# switch_AT10.net
KiCad netlist of a schematic drawn in EAGLE
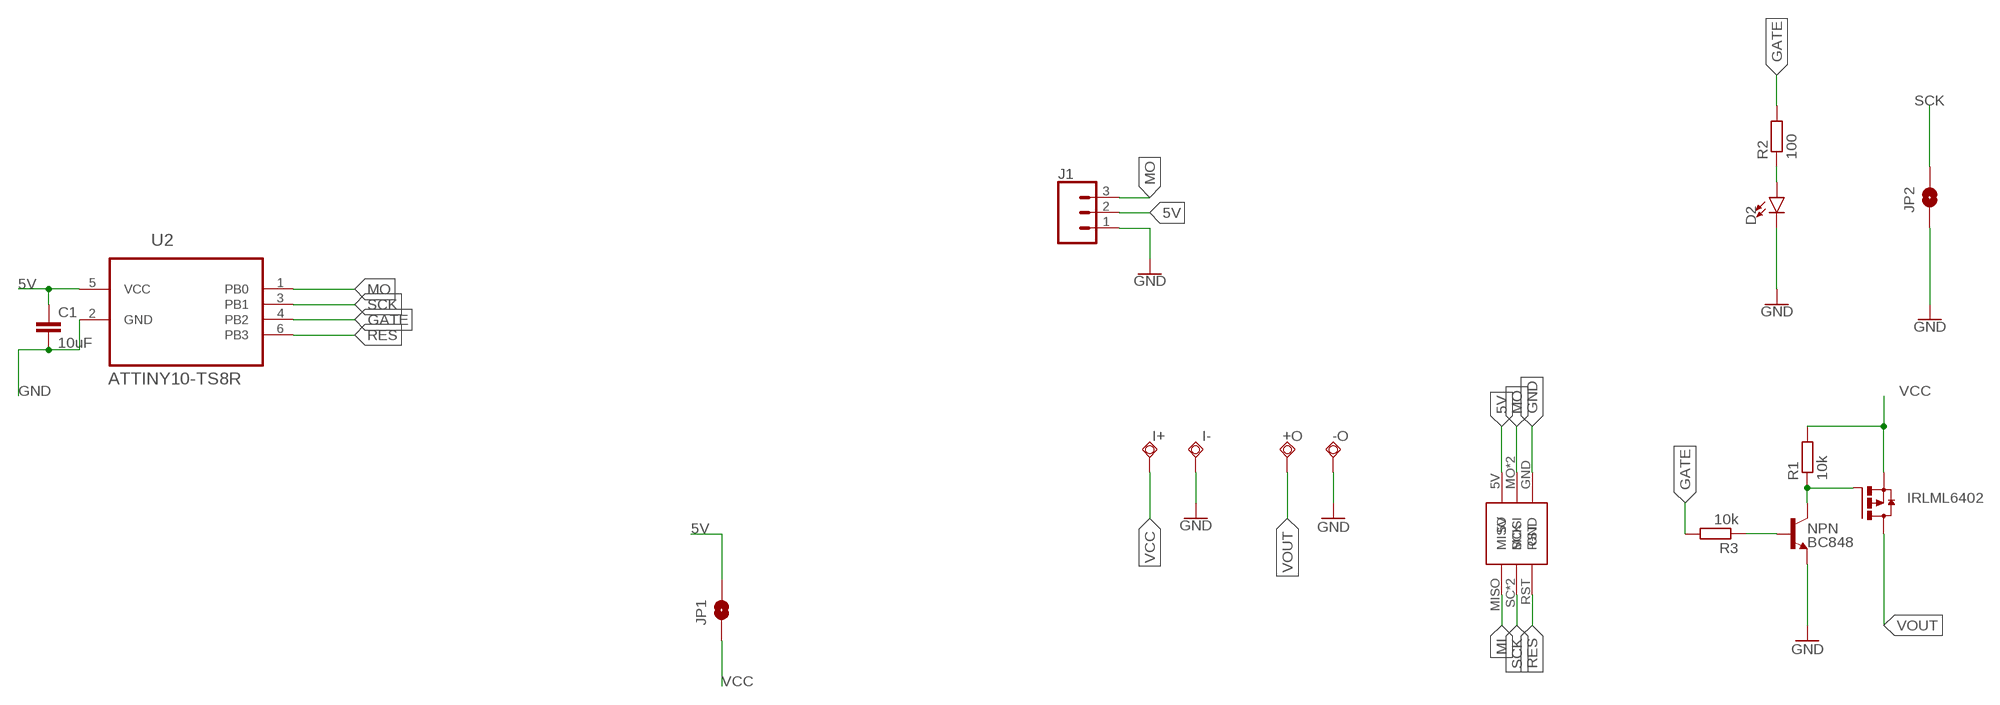
[diagram p0: schematic, sheet 1]

(export (version "E")
  (design (tool "Eeschema 10.0.6"))
  (components
    (comp (ref "+O")
      (value "TPSQTP20SQ")
      (footprint "eagle-import:TP20SQ")
      (libsource (lib "eagle-import") (part "TPSQTP20SQ"))
    )
    (comp (ref "-O")
      (value "TPSQTP20SQ")
      (footprint "eagle-import:TP20SQ")
      (libsource (lib "eagle-import") (part "TPSQTP20SQ"))
    )
    (comp (ref "C1")
      (value "10uF")
      (footprint "eagle-import:C0603K")
      (libsource (lib "eagle-import") (part "C-EUC0603K"))
    )
    (comp (ref "D2")
      (value "LED0603")
      (footprint "eagle-import:LED-0603")
      (libsource (lib "eagle-import") (part "LED0603"))
    )
    (comp (ref "I+")
      (value "TPSQTP20SQ")
      (footprint "eagle-import:TP20SQ")
      (libsource (lib "eagle-import") (part "TPSQTP20SQ"))
    )
    (comp (ref "I-")
      (value "TPSQTP20SQ")
      (footprint "eagle-import:TP20SQ")
      (libsource (lib "eagle-import") (part "TPSQTP20SQ"))
    )
    (comp (ref "IRLML6402")
      (value "FDN360P")
      (footprint "eagle-import:SUPER-SOT3")
      (libsource (lib "eagle-import") (part "FDN360P"))
    )
    (comp (ref "J1")
      (value "CONN_03")
      (footprint "eagle-import:1X03")
      (libsource (lib "eagle-import") (part "CONN_03"))
    )
    (comp (ref "JP1")
      (value "JUMPER-SMT_2_NO_NO-SILK")
      (footprint "eagle-import:SMT-JUMPER_2_NO_NO-SILK")
      (libsource (lib "eagle-import") (part "JUMPER-SMT_2_NO_NO-SILK"))
    )
    (comp (ref "JP2")
      (value "JUMPER-SMT_2_NO_NO-SILK")
      (footprint "eagle-import:SMT-JUMPER_2_NO_NO-SILK")
      (libsource (lib "eagle-import") (part "JUMPER-SMT_2_NO_NO-SILK"))
    )
    (comp (ref "NPN")
      (value "BC848")
      (footprint "eagle-import:SOT23-3")
      (libsource (lib "eagle-import") (part "TRANS_NPN-MMBT2222AL"))
    )
    (comp (ref "R1")
      (value "10k")
      (footprint "eagle-import:R0603")
      (libsource (lib "eagle-import") (part "R-EU_R0603"))
    )
    (comp (ref "R2")
      (value "100")
      (footprint "eagle-import:R0603")
      (libsource (lib "eagle-import") (part "R-EU_R0603"))
    )
    (comp (ref "R3")
      (value "10k")
      (footprint "eagle-import:R0603")
      (libsource (lib "eagle-import") (part "R-EU_R0603"))
    )
    (comp (ref "U$2")
      (value "ISCP_PORTPOGONEW")
      (footprint "eagle-import:ISCP_PADS_2ROW2HNEW")
      (libsource (lib "eagle-import") (part "ISCP_PORTPOGONEW"))
    )
    (comp (ref "U2")
      (value "ATTINY10-TS8R")
      (footprint "eagle-import:SOT95P280X145-6N")
      (fields (field (name "MF") "Microchip"))
      (libsource (lib "eagle-import") (part "ATTINY10-TS8R"))
    )
  )
  (nets
    (net (code "1") (name "5V") (class "Default")
      (node (ref "C1") (pin "1") (pinfunction "1_1") (pintype "passive"))
      (node (ref "J1") (pin "2") (pinfunction "2_2") (pintype "passive"))
      (node (ref "JP1") (pin "2") (pinfunction "2_2") (pintype "passive"))
      (node (ref "U$2") (pin "5V") (pinfunction "5V_5V") (pintype "bidirectional"))
      (node (ref "U2") (pin "5") (pinfunction "VCC_5") (pintype "power_in"))
    )
    (net (code "2") (name "GATE") (class "Default")
      (node (ref "R2") (pin "2") (pinfunction "2_2") (pintype "passive"))
      (node (ref "R3") (pin "2") (pinfunction "2_2") (pintype "passive"))
      (node (ref "U2") (pin "4") (pinfunction "PB2_4") (pintype "bidirectional"))
    )
    (net (code "3") (name "GND") (class "Default")
      (node (ref "-O") (pin "TP") (pinfunction "TP_TP") (pintype "input"))
      (node (ref "C1") (pin "2") (pinfunction "2_2") (pintype "passive"))
      (node (ref "D2") (pin "C") (pinfunction "C_C") (pintype "passive"))
      (node (ref "I-") (pin "TP") (pinfunction "TP_TP") (pintype "input"))
      (node (ref "J1") (pin "1") (pinfunction "1_1") (pintype "passive"))
      (node (ref "JP2") (pin "1") (pinfunction "1_1") (pintype "passive"))
      (node (ref "NPN") (pin "2") (pinfunction "E_2") (pintype "passive"))
      (node (ref "U$2") (pin "GND") (pinfunction "GND_GND") (pintype "bidirectional"))
      (node (ref "U2") (pin "2") (pinfunction "GND_2") (pintype "passive"))
    )
    (net (code "4") (name "MI") (class "Default")
      (node (ref "U$2") (pin "MISO") (pinfunction "MISO_MISO") (pintype "bidirectional"))
    )
    (net (code "5") (name "MO") (class "Default")
      (node (ref "J1") (pin "3") (pinfunction "3_3") (pintype "passive"))
      (node (ref "U$2") (pin "MO") (pinfunction "MOSI_MO") (pintype "bidirectional"))
      (node (ref "U$2") (pin "MOSI") (pinfunction "MOSI_MOSI") (pintype "bidirectional"))
      (node (ref "U2") (pin "1") (pinfunction "PB0_1") (pintype "bidirectional"))
    )
    (net (code "6") (name "Net-(D2-PadA)") (class "Default")
      (node (ref "D2") (pin "A") (pinfunction "A_A") (pintype "passive"))
      (node (ref "R2") (pin "1") (pinfunction "1_1") (pintype "passive"))
    )
    (net (code "7") (name "Net-(IRLML6402-G)") (class "Default")
      (node (ref "IRLML6402") (pin "1") (pinfunction "G_1") (pintype "passive"))
      (node (ref "NPN") (pin "3") (pinfunction "C_3") (pintype "passive"))
      (node (ref "R1") (pin "1") (pinfunction "1_1") (pintype "passive"))
    )
    (net (code "8") (name "Net-(NPN-B)") (class "Default")
      (node (ref "NPN") (pin "1") (pinfunction "B_1") (pintype "passive"))
      (node (ref "R3") (pin "1") (pinfunction "1_1") (pintype "passive"))
    )
    (net (code "9") (name "RES") (class "Default")
      (node (ref "U$2") (pin "RST") (pinfunction "RST_RST") (pintype "bidirectional"))
      (node (ref "U2") (pin "6") (pinfunction "PB3_6") (pintype "bidirectional"))
    )
    (net (code "10") (name "SCK") (class "Default")
      (node (ref "JP2") (pin "2") (pinfunction "2_2") (pintype "passive"))
      (node (ref "U$2") (pin "SC") (pinfunction "SCK_SC") (pintype "bidirectional"))
      (node (ref "U$2") (pin "SCK") (pinfunction "SCK_SCK") (pintype "bidirectional"))
      (node (ref "U2") (pin "3") (pinfunction "PB1_3") (pintype "bidirectional"))
    )
    (net (code "11") (name "VCC") (class "Default")
      (node (ref "I+") (pin "TP") (pinfunction "TP_TP") (pintype "input"))
      (node (ref "IRLML6402") (pin "2") (pinfunction "S_2") (pintype "passive"))
      (node (ref "JP1") (pin "1") (pinfunction "1_1") (pintype "passive"))
      (node (ref "R1") (pin "2") (pinfunction "2_2") (pintype "passive"))
    )
    (net (code "12") (name "VOUT") (class "Default")
      (node (ref "+O") (pin "TP") (pinfunction "TP_TP") (pintype "input"))
      (node (ref "IRLML6402") (pin "3") (pinfunction "D_3") (pintype "passive"))
    )
  )
)
